# RSP2NRF.net
KiCad netlist of a schematic drawn in EAGLE
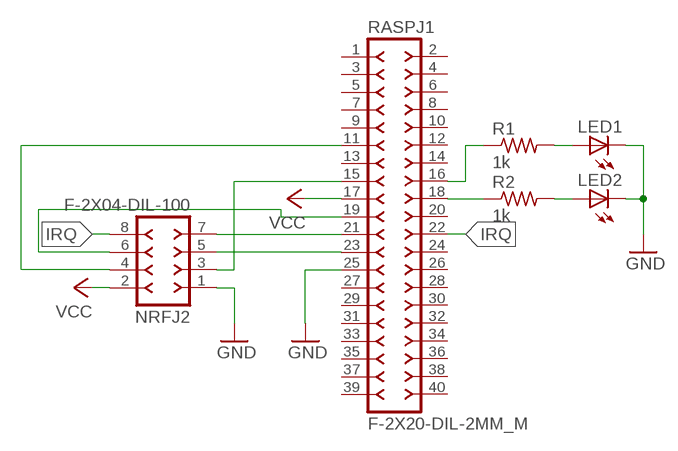
[diagram p0: schematic, sheet 1]

(export (version "E")
  (design (tool "Eeschema 10.0.6"))
  (components
    (comp (ref "LED1")
      (value "LEDCHIPLED_0805")
      (footprint "eagle-import:CHIPLED_0805")
      (fields (field (name "MPN") "OVS-0808"))
      (libsource (lib "eagle-import") (part "LEDCHIPLED_0805"))
    )
    (comp (ref "LED2")
      (value "LEDCHIPLED_0805")
      (footprint "eagle-import:CHIPLED_0805")
      (fields (field (name "MPN") "OVS-0808"))
      (libsource (lib "eagle-import") (part "LEDCHIPLED_0805"))
    )
    (comp (ref "NRFJ2")
      (value "F-2X04-DIL-100")
      (footprint "eagle-import:DIL-100-2X04")
      (libsource (lib "eagle-import") (part "F-2X04-DIL-100"))
    )
    (comp (ref "R1")
      (value "1k")
      (footprint "eagle-import:R0805")
      (fields (field (name "MF") "VISHAY/DALE") (field (name "MPN") "CRCW20101K00FKEF"))
      (libsource (lib "eagle-import") (part "R-US_R0805"))
    )
    (comp (ref "R2")
      (value "1k")
      (footprint "eagle-import:R0805")
      (fields (field (name "MF") "VISHAY/DALE") (field (name "MPN") "CRCW20101K00FKEF"))
      (libsource (lib "eagle-import") (part "R-US_R0805"))
    )
    (comp (ref "RASPJ1")
      (value "F-2X20-DIL-2MM_M")
      (footprint "eagle-import:DIL-2MM-2X20_M")
      (libsource (lib "eagle-import") (part "F-2X20-DIL-2MM_M"))
    )
  )
  (nets
    (net (code "1") (name "GND") (class "Default")
      (node (ref "LED1") (pin "C") (pinfunction "C_C") (pintype "passive"))
      (node (ref "LED2") (pin "C") (pinfunction "C_C") (pintype "passive"))
      (node (ref "NRFJ2") (pin "1") (pinfunction "1_1") (pintype "passive"))
      (node (ref "RASPJ1") (pin "25") (pinfunction "25_25") (pintype "passive"))
    )
    (net (code "2") (name "IRQ") (class "Default")
      (node (ref "NRFJ2") (pin "8") (pinfunction "8_8") (pintype "passive"))
      (node (ref "RASPJ1") (pin "22") (pinfunction "22_22") (pintype "passive"))
    )
    (net (code "3") (name "Net-(LED1-PadA)") (class "Default")
      (node (ref "LED1") (pin "A") (pinfunction "A_A") (pintype "passive"))
      (node (ref "R1") (pin "2") (pinfunction "2_2") (pintype "passive"))
    )
    (net (code "4") (name "Net-(LED2-PadA)") (class "Default")
      (node (ref "LED2") (pin "A") (pinfunction "A_A") (pintype "passive"))
      (node (ref "R2") (pin "2") (pinfunction "2_2") (pintype "passive"))
    )
    (net (code "5") (name "Net-(NRFJ2-Pad3)") (class "Default")
      (node (ref "NRFJ2") (pin "3") (pinfunction "3_3") (pintype "passive"))
      (node (ref "RASPJ1") (pin "15") (pinfunction "15_15") (pintype "passive"))
    )
    (net (code "6") (name "Net-(NRFJ2-Pad4)") (class "Default")
      (node (ref "NRFJ2") (pin "4") (pinfunction "4_4") (pintype "passive"))
      (node (ref "RASPJ1") (pin "11") (pinfunction "11_11") (pintype "passive"))
    )
    (net (code "7") (name "Net-(NRFJ2-Pad5)") (class "Default")
      (node (ref "NRFJ2") (pin "5") (pinfunction "5_5") (pintype "passive"))
      (node (ref "RASPJ1") (pin "23") (pinfunction "23_23") (pintype "passive"))
    )
    (net (code "8") (name "Net-(NRFJ2-Pad6)") (class "Default")
      (node (ref "NRFJ2") (pin "6") (pinfunction "6_6") (pintype "passive"))
      (node (ref "RASPJ1") (pin "19") (pinfunction "19_19") (pintype "passive"))
    )
    (net (code "9") (name "Net-(NRFJ2-Pad7)") (class "Default")
      (node (ref "NRFJ2") (pin "7") (pinfunction "7_7") (pintype "passive"))
      (node (ref "RASPJ1") (pin "21") (pinfunction "21_21") (pintype "passive"))
    )
    (net (code "10") (name "Net-(R1-Pad1)") (class "Default")
      (node (ref "R1") (pin "1") (pinfunction "1_1") (pintype "passive"))
      (node (ref "RASPJ1") (pin "16") (pinfunction "16_16") (pintype "passive"))
    )
    (net (code "11") (name "Net-(R2-Pad1)") (class "Default")
      (node (ref "R2") (pin "1") (pinfunction "1_1") (pintype "passive"))
      (node (ref "RASPJ1") (pin "18") (pinfunction "18_18") (pintype "passive"))
    )
    (net (code "12") (name "VCC") (class "Default")
      (node (ref "NRFJ2") (pin "2") (pinfunction "2_2") (pintype "passive"))
      (node (ref "RASPJ1") (pin "17") (pinfunction "17_17") (pintype "passive"))
    )
    (net (code "13") (name "unconnected-(RASPJ1-Pad1)") (class "Default")
      (node (ref "RASPJ1") (pin "1") (pinfunction "1_1") (pintype "passive"))
    )
    (net (code "14") (name "unconnected-(RASPJ1-Pad2)") (class "Default")
      (node (ref "RASPJ1") (pin "2") (pinfunction "2_2") (pintype "passive"))
    )
    (net (code "15") (name "unconnected-(RASPJ1-Pad3)") (class "Default")
      (node (ref "RASPJ1") (pin "3") (pinfunction "3_3") (pintype "passive"))
    )
    (net (code "16") (name "unconnected-(RASPJ1-Pad4)") (class "Default")
      (node (ref "RASPJ1") (pin "4") (pinfunction "4_4") (pintype "passive"))
    )
    (net (code "17") (name "unconnected-(RASPJ1-Pad5)") (class "Default")
      (node (ref "RASPJ1") (pin "5") (pinfunction "5_5") (pintype "passive"))
    )
    (net (code "18") (name "unconnected-(RASPJ1-Pad6)") (class "Default")
      (node (ref "RASPJ1") (pin "6") (pinfunction "6_6") (pintype "passive"))
    )
    (net (code "19") (name "unconnected-(RASPJ1-Pad7)") (class "Default")
      (node (ref "RASPJ1") (pin "7") (pinfunction "7_7") (pintype "passive"))
    )
    (net (code "20") (name "unconnected-(RASPJ1-Pad8)") (class "Default")
      (node (ref "RASPJ1") (pin "8") (pinfunction "8_8") (pintype "passive"))
    )
    (net (code "21") (name "unconnected-(RASPJ1-Pad9)") (class "Default")
      (node (ref "RASPJ1") (pin "9") (pinfunction "9_9") (pintype "passive"))
    )
    (net (code "22") (name "unconnected-(RASPJ1-Pad10)") (class "Default")
      (node (ref "RASPJ1") (pin "10") (pinfunction "10_10") (pintype "passive"))
    )
    (net (code "23") (name "unconnected-(RASPJ1-Pad12)") (class "Default")
      (node (ref "RASPJ1") (pin "12") (pinfunction "12_12") (pintype "passive"))
    )
    (net (code "24") (name "unconnected-(RASPJ1-Pad13)") (class "Default")
      (node (ref "RASPJ1") (pin "13") (pinfunction "13_13") (pintype "passive"))
    )
    (net (code "25") (name "unconnected-(RASPJ1-Pad14)") (class "Default")
      (node (ref "RASPJ1") (pin "14") (pinfunction "14_14") (pintype "passive"))
    )
    (net (code "26") (name "unconnected-(RASPJ1-Pad20)") (class "Default")
      (node (ref "RASPJ1") (pin "20") (pinfunction "20_20") (pintype "passive"))
    )
    (net (code "27") (name "unconnected-(RASPJ1-Pad24)") (class "Default")
      (node (ref "RASPJ1") (pin "24") (pinfunction "24_24") (pintype "passive"))
    )
    (net (code "28") (name "unconnected-(RASPJ1-Pad26)") (class "Default")
      (node (ref "RASPJ1") (pin "26") (pinfunction "26_26") (pintype "passive"))
    )
    (net (code "29") (name "unconnected-(RASPJ1-Pad27)") (class "Default")
      (node (ref "RASPJ1") (pin "27") (pinfunction "27_27") (pintype "passive"))
    )
    (net (code "30") (name "unconnected-(RASPJ1-Pad28)") (class "Default")
      (node (ref "RASPJ1") (pin "28") (pinfunction "28_28") (pintype "passive"))
    )
    (net (code "31") (name "unconnected-(RASPJ1-Pad29)") (class "Default")
      (node (ref "RASPJ1") (pin "29") (pinfunction "29_29") (pintype "passive"))
    )
    (net (code "32") (name "unconnected-(RASPJ1-Pad30)") (class "Default")
      (node (ref "RASPJ1") (pin "30") (pinfunction "30_30") (pintype "passive"))
    )
    (net (code "33") (name "unconnected-(RASPJ1-Pad31)") (class "Default")
      (node (ref "RASPJ1") (pin "31") (pinfunction "31_31") (pintype "passive"))
    )
    (net (code "34") (name "unconnected-(RASPJ1-Pad32)") (class "Default")
      (node (ref "RASPJ1") (pin "32") (pinfunction "32_32") (pintype "passive"))
    )
    (net (code "35") (name "unconnected-(RASPJ1-Pad33)") (class "Default")
      (node (ref "RASPJ1") (pin "33") (pinfunction "33_33") (pintype "passive"))
    )
    (net (code "36") (name "unconnected-(RASPJ1-Pad34)") (class "Default")
      (node (ref "RASPJ1") (pin "34") (pinfunction "34_34") (pintype "passive"))
    )
    (net (code "37") (name "unconnected-(RASPJ1-Pad35)") (class "Default")
      (node (ref "RASPJ1") (pin "35") (pinfunction "35_35") (pintype "passive"))
    )
    (net (code "38") (name "unconnected-(RASPJ1-Pad36)") (class "Default")
      (node (ref "RASPJ1") (pin "36") (pinfunction "36_36") (pintype "passive"))
    )
    (net (code "39") (name "unconnected-(RASPJ1-Pad37)") (class "Default")
      (node (ref "RASPJ1") (pin "37") (pinfunction "37_37") (pintype "passive"))
    )
    (net (code "40") (name "unconnected-(RASPJ1-Pad38)") (class "Default")
      (node (ref "RASPJ1") (pin "38") (pinfunction "38_38") (pintype "passive"))
    )
    (net (code "41") (name "unconnected-(RASPJ1-Pad39)") (class "Default")
      (node (ref "RASPJ1") (pin "39") (pinfunction "39_39") (pintype "passive"))
    )
    (net (code "42") (name "unconnected-(RASPJ1-Pad40)") (class "Default")
      (node (ref "RASPJ1") (pin "40") (pinfunction "40_40") (pintype "passive"))
    )
  )
)
